# Sheet1.net
KiCad netlist of a schematic drawn in Altium Designer
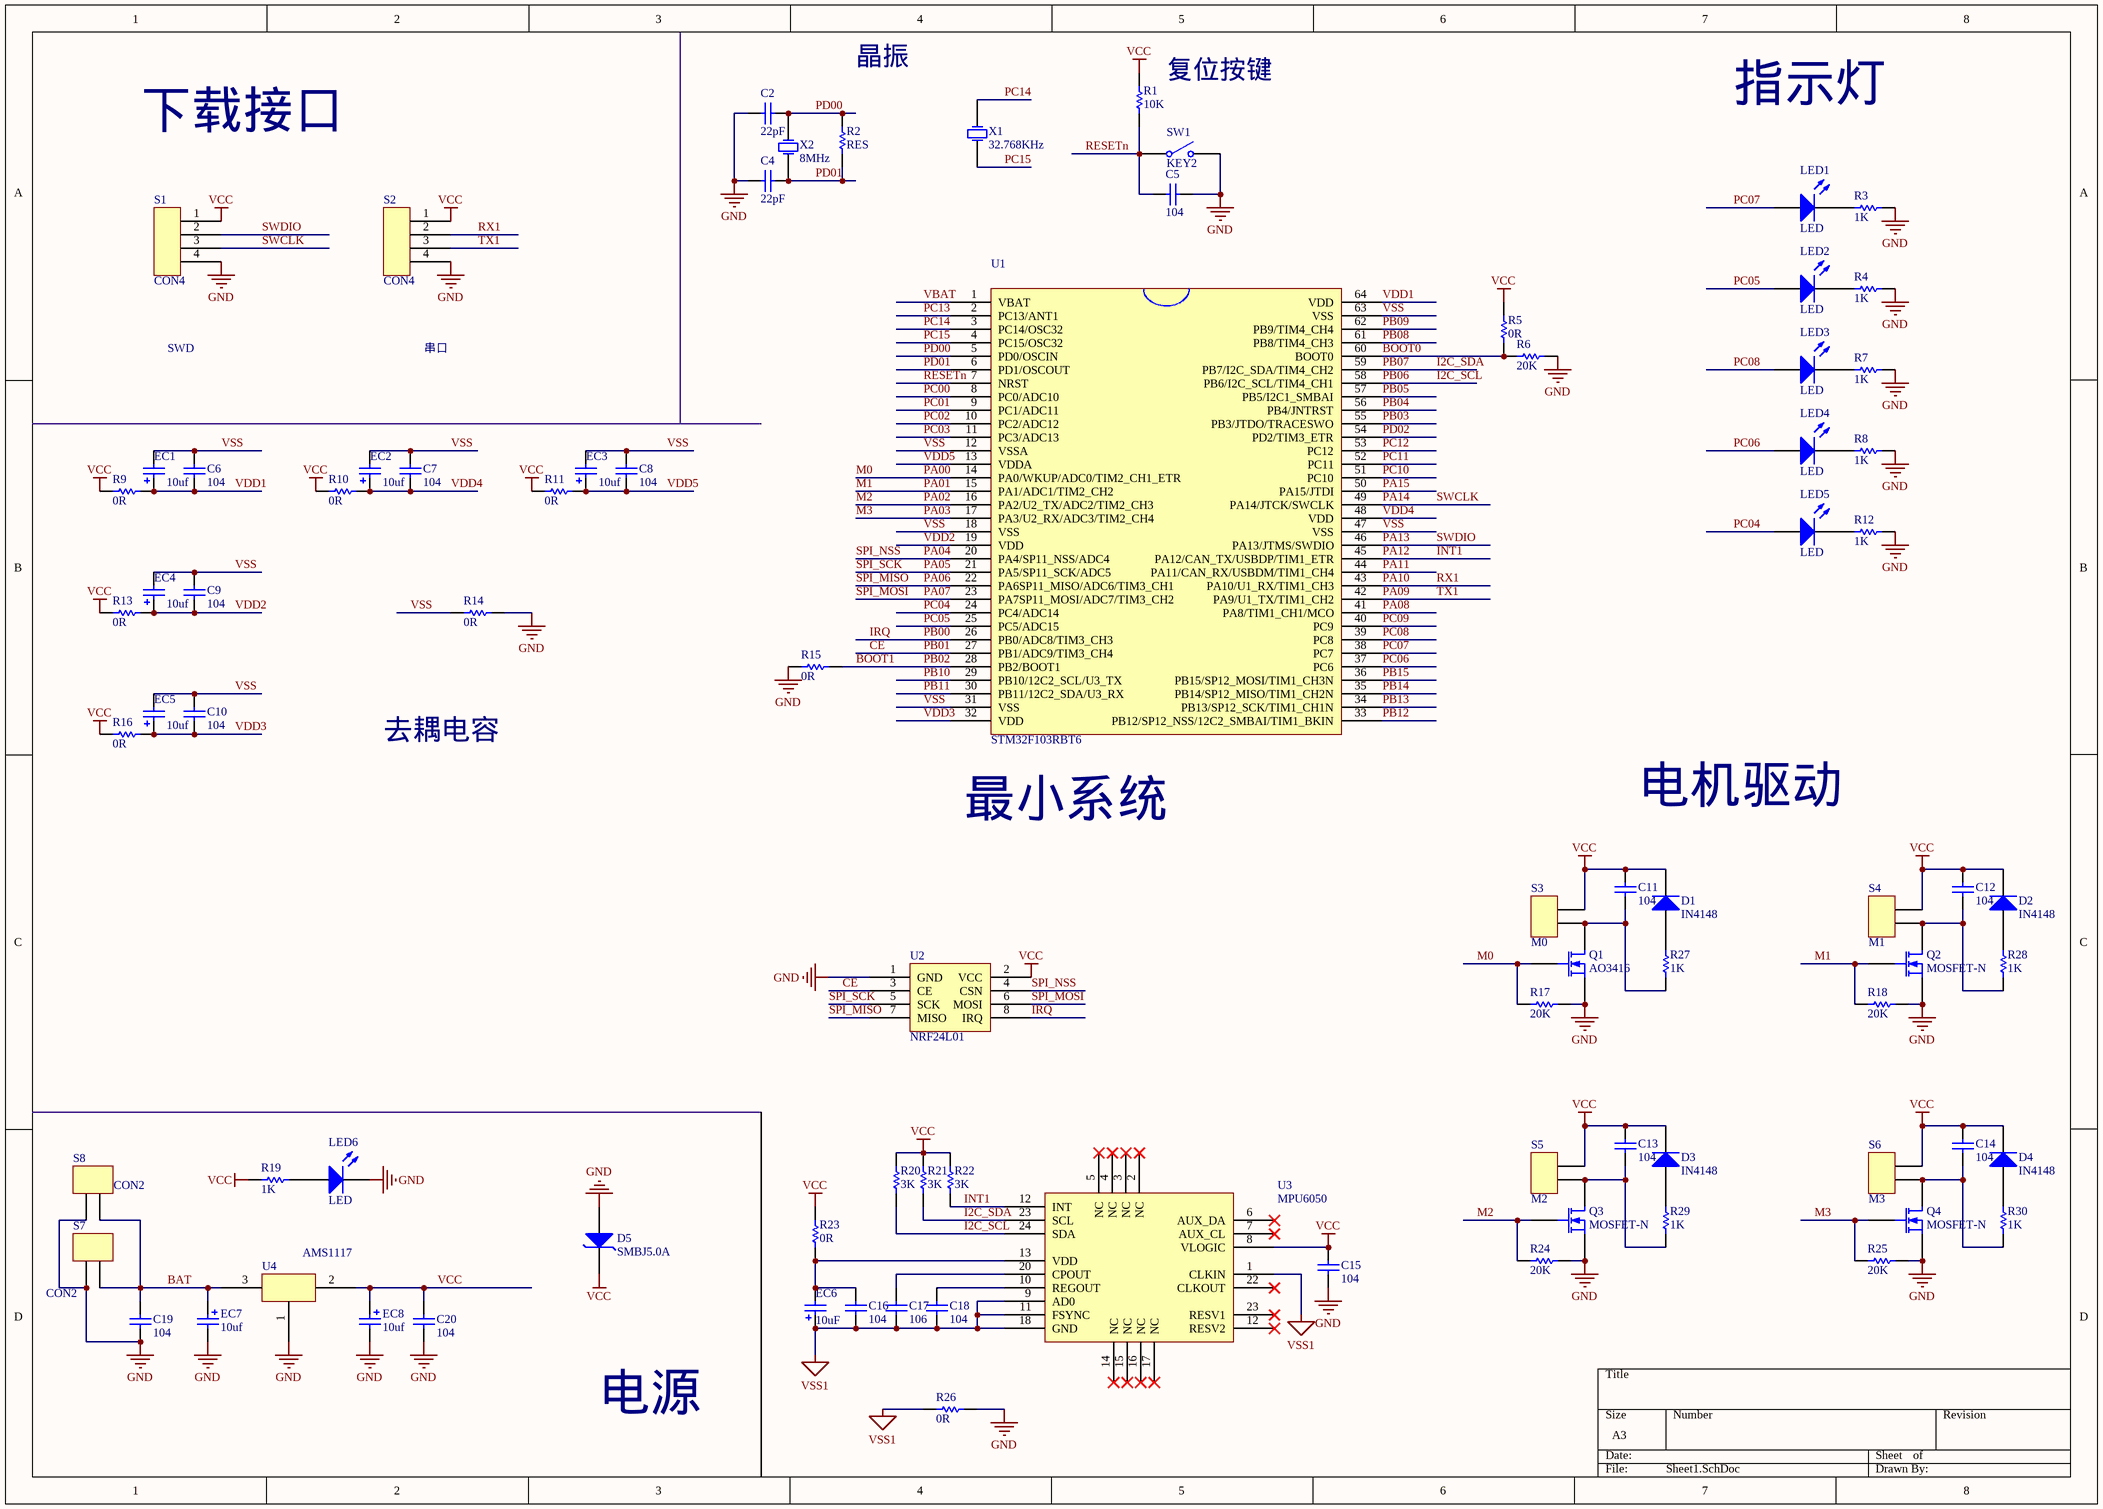
[diagram p0: Sheet1.SchDoc]

(export (version "E")
  (design (tool "Eeschema 10.0.6"))
  (components
    (comp (ref "C2") (value "22pF") (footprint "0805") (libsource (lib "yezi_sch") (part "CAP")))
    (comp (ref "C4") (value "22pF") (footprint "0805") (libsource (lib "yezi_sch") (part "CAP")))
    (comp (ref "C5") (value "104") (footprint "0603") (libsource (lib "yezi_sch") (part "CAP")))
    (comp (ref "C6") (value "104") (footprint "0603") (libsource (lib "yezi_sch") (part "CAP")))
    (comp (ref "C7") (value "104") (footprint "0603") (libsource (lib "yezi_sch") (part "CAP")))
    (comp (ref "C8") (value "104") (footprint "0603") (libsource (lib "yezi_sch") (part "CAP")))
    (comp (ref "C9") (value "104") (footprint "0603") (libsource (lib "yezi_sch") (part "CAP")))
    (comp (ref "C10") (value "104") (footprint "0603") (libsource (lib "yezi_sch") (part "CAP")))
    (comp (ref "C11") (value "104") (footprint "0603") (libsource (lib "yezi_sch") (part "CAP")))
    (comp (ref "C12") (value "104") (footprint "0603") (libsource (lib "yezi_sch") (part "CAP")))
    (comp (ref "C13") (value "104") (footprint "0603") (libsource (lib "yezi_sch") (part "CAP")))
    (comp (ref "C14") (value "104") (footprint "0603") (libsource (lib "yezi_sch") (part "CAP")))
    (comp (ref "C15") (value "104") (footprint "0603") (libsource (lib "yezi_sch") (part "CAP")))
    (comp (ref "C16") (value "104") (footprint "0603") (libsource (lib "yezi_sch") (part "CAP")))
    (comp (ref "C17") (value "106") (footprint "0805") (libsource (lib "yezi_sch") (part "CAP")))
    (comp (ref "C18") (value "104") (footprint "0603") (libsource (lib "yezi_sch") (part "CAP")))
    (comp (ref "C19") (value "104") (footprint "0603") (libsource (lib "yezi_sch") (part "CAP")))
    (comp (ref "C20") (value "104") (footprint "0603") (libsource (lib "yezi_sch") (part "CAP")))
    (comp (ref "D1") (value "IN4148") (footprint "1206") (libsource (lib "yezi_sch") (part "DIODE")))
    (comp (ref "D2") (value "IN4148") (footprint "1206") (libsource (lib "yezi_sch") (part "DIODE")))
    (comp (ref "D3") (value "IN4148") (footprint "1206") (libsource (lib "yezi_sch") (part "DIODE")))
    (comp (ref "D4") (value "IN4148") (footprint "1206") (libsource (lib "yezi_sch") (part "DIODE")))
    (comp (ref "D5")
      (value "SMBJ5.0A")
      (footprint "DIOM4436X23N")
      (libsource (lib "yezi_sch") (part "SMBJ5.0A"))
    )
    (comp (ref "EC1") (value "10uf") (footprint "1206") (libsource (lib "yezi_sch") (part "EC")))
    (comp (ref "EC2") (value "10uf") (footprint "1206") (libsource (lib "yezi_sch") (part "EC")))
    (comp (ref "EC3") (value "10uf") (footprint "1206") (libsource (lib "yezi_sch") (part "EC")))
    (comp (ref "EC4") (value "10uf") (footprint "1206") (libsource (lib "yezi_sch") (part "EC")))
    (comp (ref "EC5") (value "10uf") (footprint "1206") (libsource (lib "yezi_sch") (part "EC")))
    (comp (ref "EC6") (value "10uF") (footprint "1206") (libsource (lib "yezi_sch") (part "EC")))
    (comp (ref "EC7") (value "10uf") (footprint "1206") (libsource (lib "yezi_sch") (part "EC")))
    (comp (ref "EC8") (value "10uf") (footprint "1206") (libsource (lib "yezi_sch") (part "EC")))
    (comp (ref "LED1") (value "LED") (footprint "0805") (libsource (lib "yezi_sch") (part "LED")))
    (comp (ref "LED2") (value "LED") (footprint "0805") (libsource (lib "yezi_sch") (part "LED")))
    (comp (ref "LED3") (value "LED") (footprint "0805") (libsource (lib "yezi_sch") (part "LED")))
    (comp (ref "LED4") (value "LED") (footprint "0805") (libsource (lib "yezi_sch") (part "LED")))
    (comp (ref "LED5") (value "LED") (footprint "0805") (libsource (lib "yezi_sch") (part "LED")))
    (comp (ref "LED6") (value "LED") (footprint "0805") (libsource (lib "yezi_sch") (part "LED")))
    (comp (ref "Q1")
      (value "AO3416")
      (footprint "SOT-23_N")
      (description "N-Channel MOSFET")
      (fields (field (name "PUBLISHER") "Altium Limited"))
      (libsource (lib "yezi_sch") (part "MOSFET-N"))
    )
    (comp (ref "Q2")
      (value "MOSFET-N")
      (footprint "SOT-23_N")
      (description "N-Channel MOSFET")
      (fields (field (name "PUBLISHER") "Altium Limited"))
      (libsource (lib "yezi_sch") (part "MOSFET-N"))
    )
    (comp (ref "Q3")
      (value "MOSFET-N")
      (footprint "SOT-23_N")
      (description "N-Channel MOSFET")
      (fields (field (name "PUBLISHER") "Altium Limited"))
      (libsource (lib "yezi_sch") (part "MOSFET-N"))
    )
    (comp (ref "Q4")
      (value "MOSFET-N")
      (footprint "SOT-23_N")
      (description "N-Channel MOSFET")
      (fields (field (name "PUBLISHER") "Altium Limited"))
      (libsource (lib "yezi_sch") (part "MOSFET-N"))
    )
    (comp (ref "R1") (value "10K") (footprint "0603") (libsource (lib "yezi_sch") (part "RES")))
    (comp (ref "R2") (value "RES") (footprint "0805") (libsource (lib "yezi_sch") (part "RES")))
    (comp (ref "R3") (value "1K") (footprint "0603") (libsource (lib "yezi_sch") (part "RES")))
    (comp (ref "R4") (value "1K") (footprint "0603") (libsource (lib "yezi_sch") (part "RES")))
    (comp (ref "R5") (value "0R") (footprint "0603") (libsource (lib "yezi_sch") (part "RES")))
    (comp (ref "R6") (value "20K") (footprint "0603") (libsource (lib "yezi_sch") (part "RES")))
    (comp (ref "R7") (value "1K") (footprint "0603") (libsource (lib "yezi_sch") (part "RES")))
    (comp (ref "R8") (value "1K") (footprint "0603") (libsource (lib "yezi_sch") (part "RES")))
    (comp (ref "R9") (value "0R") (footprint "0603") (libsource (lib "yezi_sch") (part "RES")))
    (comp (ref "R10") (value "0R") (footprint "0603") (libsource (lib "yezi_sch") (part "RES")))
    (comp (ref "R11") (value "0R") (footprint "0603") (libsource (lib "yezi_sch") (part "RES")))
    (comp (ref "R12") (value "1K") (footprint "0603") (libsource (lib "yezi_sch") (part "RES")))
    (comp (ref "R13") (value "0R") (footprint "0603") (libsource (lib "yezi_sch") (part "RES")))
    (comp (ref "R14") (value "0R") (footprint "0603") (libsource (lib "yezi_sch") (part "RES")))
    (comp (ref "R15") (value "0R") (footprint "0603") (libsource (lib "yezi_sch") (part "RES")))
    (comp (ref "R16") (value "0R") (footprint "0603") (libsource (lib "yezi_sch") (part "RES")))
    (comp (ref "R17") (value "20K") (footprint "0603") (libsource (lib "yezi_sch") (part "RES")))
    (comp (ref "R18") (value "20K") (footprint "0603") (libsource (lib "yezi_sch") (part "RES")))
    (comp (ref "R19") (value "1K") (footprint "0603") (libsource (lib "yezi_sch") (part "RES")))
    (comp (ref "R20") (value "3K") (footprint "0603") (libsource (lib "yezi_sch") (part "RES")))
    (comp (ref "R21") (value "3K") (footprint "0603") (libsource (lib "yezi_sch") (part "RES")))
    (comp (ref "R22") (value "3K") (footprint "0603") (libsource (lib "yezi_sch") (part "RES")))
    (comp (ref "R23") (value "0R") (footprint "0603") (libsource (lib "yezi_sch") (part "RES")))
    (comp (ref "R24") (value "20K") (footprint "0603") (libsource (lib "yezi_sch") (part "RES")))
    (comp (ref "R25") (value "20K") (footprint "0603") (libsource (lib "yezi_sch") (part "RES")))
    (comp (ref "R26") (value "0R") (footprint "0603") (libsource (lib "yezi_sch") (part "RES")))
    (comp (ref "R27") (value "1K") (footprint "0603") (libsource (lib "yezi_sch") (part "RES")))
    (comp (ref "R28") (value "1K") (footprint "0603") (libsource (lib "yezi_sch") (part "RES")))
    (comp (ref "R29") (value "1K") (footprint "0603") (libsource (lib "yezi_sch") (part "RES")))
    (comp (ref "R30") (value "1K") (footprint "0603") (libsource (lib "yezi_sch") (part "RES")))
    (comp (ref "S1") (value "CON4") (footprint "SIP4") (libsource (lib "yezi_sch") (part "CON4")))
    (comp (ref "S2") (value "CON4") (footprint "SIP4") (libsource (lib "yezi_sch") (part "CON4")))
    (comp (ref "S3") (value "M0") (footprint "0805") (libsource (lib "yezi_sch") (part "CON2")))
    (comp (ref "S4") (value "M1") (footprint "0805") (libsource (lib "yezi_sch") (part "CON2")))
    (comp (ref "S5") (value "M2") (footprint "0805") (libsource (lib "yezi_sch") (part "CON2")))
    (comp (ref "S6") (value "M3") (footprint "0805") (libsource (lib "yezi_sch") (part "CON2")))
    (comp (ref "S7") (value "CON2") (footprint "1206") (libsource (lib "") (part "CON2_1")))
    (comp (ref "S8") (value "CON2") (footprint "SIP2") (libsource (lib "") (part "CON2_1")))
    (comp (ref "SW1") (value "KEY2") (footprint "SSOP2N") (libsource (lib "yezi_sch") (part "KEY2")))
    (comp (ref "U1")
      (value "STM32F103RBT6")
      (footprint "TSQFP50P1200X1200X160-64N")
      (libsource (lib "yezi_sch") (part "STM32F103RBT6"))
    )
    (comp (ref "U2") (value "NRF24L01") (footprint "CN8") (libsource (lib "yezi_sch") (part "NRF24L01")))
    (comp (ref "U3")
      (value "MPU6050")
      (footprint "QFN50P400X400X95_HS-25N")
      (libsource (lib "yezi_sch") (part "MPU6050"))
    )
    (comp (ref "U4") (value "AMS1117") (footprint "SOT223") (libsource (lib "yezi_sch") (part "AMS1117")))
    (comp (ref "X1") (value "32.768KHz") (footprint "XTAL-50-2") (libsource (lib "yezi_sch") (part "XTAL")))
    (comp (ref "X2") (value "8MHz") (footprint "XTAL-200") (libsource (lib "yezi_sch") (part "XTAL")))
  )
  (nets
    (net (code "1") (name "/BAT") (class "Default")
      (node (ref "C19") (pin "1") (pinfunction "1_1") (pintype "passive"))
      (node (ref "EC7") (pin "1") (pinfunction "1_1") (pintype "passive"))
      (node (ref "S7") (pin "1") (pinfunction "1_1") (pintype "passive"))
      (node (ref "S8") (pin "1") (pinfunction "1_1") (pintype "passive"))
      (node (ref "U4") (pin "3") (pinfunction "3_3") (pintype "passive"))
    )
    (net (code "2") (name "/BOOT0") (class "Default")
      (node (ref "R5") (pin "1") (pinfunction "1_1") (pintype "passive"))
      (node (ref "R6") (pin "1") (pinfunction "1_1") (pintype "passive"))
      (node (ref "U1") (pin "60") (pinfunction "BOOT0_60") (pintype "passive"))
    )
    (net (code "3") (name "/BOOT1") (class "Default")
      (node (ref "R15") (pin "2") (pinfunction "2_2") (pintype "passive"))
      (node (ref "U1") (pin "28") (pinfunction "PB2/BOOT1_28") (pintype "passive"))
    )
    (net (code "4") (name "/CE") (class "Default")
      (node (ref "U1") (pin "27") (pinfunction "PB1/ADC9/TIM3_CH4_27") (pintype "passive"))
      (node (ref "U2") (pin "3") (pinfunction "CE_3") (pintype "passive"))
    )
    (net (code "5") (name "/I2C_SCL") (class "Default")
      (node (ref "R20") (pin "1") (pinfunction "1_1") (pintype "passive"))
      (node (ref "U1") (pin "58") (pinfunction "PB6/I2C_SCL/TIM4_CH1_58") (pintype "passive"))
      (node (ref "U3") (pin "24") (pinfunction "SDA_24") (pintype "passive"))
    )
    (net (code "6") (name "/I2C_SDA") (class "Default")
      (node (ref "R21") (pin "1") (pinfunction "1_1") (pintype "passive"))
      (node (ref "U1") (pin "59") (pinfunction "PB7/I2C_SDA/TIM4_CH2_59") (pintype "passive"))
      (node (ref "U3") (pin "23") (pinfunction "SCL_23") (pintype "passive"))
    )
    (net (code "7") (name "/INT1") (class "Default")
      (node (ref "R22") (pin "1") (pinfunction "1_1") (pintype "passive"))
      (node (ref "U1") (pin "45") (pinfunction "PA12/CAN_TX/USBDP/TIM1_ETR_45") (pintype "passive"))
      (node (ref "U3") (pin "12") (pinfunction "INT_12") (pintype "passive"))
    )
    (net (code "8") (name "/IRQ") (class "Default")
      (node (ref "U1") (pin "26") (pinfunction "PB0/ADC8/TIM3_CH3_26") (pintype "passive"))
      (node (ref "U2") (pin "8") (pinfunction "IRQ_8") (pintype "passive"))
    )
    (net (code "9") (name "/M0") (class "Default")
      (node (ref "Q1") (pin "2") (pinfunction "G_2") (pintype "passive"))
      (node (ref "R17") (pin "1") (pinfunction "1_1") (pintype "passive"))
      (node (ref "U1") (pin "14") (pinfunction "PA0/WKUP/ADC0/TIM2_CH1_ETR_14") (pintype "passive"))
    )
    (net (code "10") (name "/M1") (class "Default")
      (node (ref "Q2") (pin "2") (pinfunction "G_2") (pintype "passive"))
      (node (ref "R18") (pin "1") (pinfunction "1_1") (pintype "passive"))
      (node (ref "U1") (pin "15") (pinfunction "PA1/ADC1/TIM2_CH2_15") (pintype "passive"))
    )
    (net (code "11") (name "/M2") (class "Default")
      (node (ref "Q3") (pin "2") (pinfunction "G_2") (pintype "passive"))
      (node (ref "R24") (pin "1") (pinfunction "1_1") (pintype "passive"))
      (node (ref "U1") (pin "16") (pinfunction "PA2/U2_TX/ADC2/TIM2_CH3_16") (pintype "passive"))
    )
    (net (code "12") (name "/M3") (class "Default")
      (node (ref "Q4") (pin "2") (pinfunction "G_2") (pintype "passive"))
      (node (ref "R25") (pin "1") (pinfunction "1_1") (pintype "passive"))
      (node (ref "U1") (pin "17") (pinfunction "PA3/U2_RX/ADC3/TIM2_CH4_17") (pintype "passive"))
    )
    (net (code "13") (name "/PA04") (class "Default")
      (node (ref "U1") (pin "20") (pinfunction "PA4/SP11_NSS/ADC4_20") (pintype "passive"))
      (node (ref "U2") (pin "4") (pinfunction "CSN_4") (pintype "passive"))
    )
    (net (code "14") (name "/PA05") (class "Default")
      (node (ref "U1") (pin "21") (pinfunction "PA5/SP11_SCK/ADC5_21") (pintype "passive"))
      (node (ref "U2") (pin "5") (pinfunction "SCK_5") (pintype "passive"))
    )
    (net (code "15") (name "/PA06") (class "Default")
      (node (ref "U1") (pin "22") (pinfunction "PA6SP11_MISO/ADC6/TIM3_CH1_22") (pintype "passive"))
      (node (ref "U2") (pin "7") (pinfunction "MISO_7") (pintype "passive"))
    )
    (net (code "16") (name "/PA07") (class "Default")
      (node (ref "U1") (pin "23") (pinfunction "PA7SP11_MOSI/ADC7/TIM3_CH2_23") (pintype "passive"))
      (node (ref "U2") (pin "6") (pinfunction "MOSI_6") (pintype "passive"))
    )
    (net (code "17") (name "/PA08") (class "Default")
      (node (ref "U1") (pin "41") (pinfunction "PA8/TIM1_CH1/MCO_41") (pintype "passive"))
    )
    (net (code "18") (name "/PA09") (class "Default")
      (node (ref "S2") (pin "3") (pinfunction "3_3") (pintype "passive"))
      (node (ref "U1") (pin "42") (pinfunction "PA9/U1_TX/TIM1_CH2_42") (pintype "passive"))
    )
    (net (code "19") (name "/PA10") (class "Default")
      (node (ref "S2") (pin "2") (pinfunction "2_2") (pintype "passive"))
      (node (ref "U1") (pin "43") (pinfunction "PA10/U1_RX/TIM1_CH3_43") (pintype "passive"))
    )
    (net (code "20") (name "/PA11") (class "Default")
      (node (ref "U1") (pin "44") (pinfunction "PA11/CAN_RX/USBDM/TIM1_CH4_44") (pintype "passive"))
    )
    (net (code "21") (name "/PA13") (class "Default")
      (node (ref "S1") (pin "2") (pinfunction "2_2") (pintype "passive"))
      (node (ref "U1") (pin "46") (pinfunction "PA13/JTMS/SWDIO_46") (pintype "passive"))
    )
    (net (code "22") (name "/PA14") (class "Default")
      (node (ref "S1") (pin "3") (pinfunction "3_3") (pintype "passive"))
      (node (ref "U1") (pin "49") (pinfunction "PA14/JTCK/SWCLK_49") (pintype "passive"))
    )
    (net (code "23") (name "/PA15") (class "Default")
      (node (ref "U1") (pin "50") (pinfunction "PA15/JTDI_50") (pintype "passive"))
    )
    (net (code "24") (name "/PB03") (class "Default")
      (node (ref "U1") (pin "55") (pinfunction "PB3/JTDO/TRACESWO_55") (pintype "passive"))
    )
    (net (code "25") (name "/PB04") (class "Default")
      (node (ref "U1") (pin "56") (pinfunction "PB4/JNTRST_56") (pintype "passive"))
    )
    (net (code "26") (name "/PB05") (class "Default")
      (node (ref "U1") (pin "57") (pinfunction "PB5/I2C1_SMBAI_57") (pintype "passive"))
    )
    (net (code "27") (name "/PB08") (class "Default")
      (node (ref "U1") (pin "61") (pinfunction "PB8/TIM4_CH3_61") (pintype "passive"))
    )
    (net (code "28") (name "/PB09") (class "Default")
      (node (ref "U1") (pin "62") (pinfunction "PB9/TIM4_CH4_62") (pintype "passive"))
    )
    (net (code "29") (name "/PB10") (class "Default")
      (node (ref "U1") (pin "29") (pinfunction "PB10/12C2_SCL/U3_TX_29") (pintype "passive"))
    )
    (net (code "30") (name "/PB11") (class "Default")
      (node (ref "U1") (pin "30") (pinfunction "PB11/12C2_SDA/U3_RX_30") (pintype "passive"))
    )
    (net (code "31") (name "/PB12") (class "Default")
      (node (ref "U1") (pin "33") (pinfunction "PB12/SP12_NSS/12C2_SMBAI/TIM1_BKIN_33") (pintype "passive"))
    )
    (net (code "32") (name "/PB13") (class "Default")
      (node (ref "U1") (pin "34") (pinfunction "PB13/SP12_SCK/TIM1_CH1N_34") (pintype "passive"))
    )
    (net (code "33") (name "/PB14") (class "Default")
      (node (ref "U1") (pin "35") (pinfunction "PB14/SP12_MISO/TIM1_CH2N_35") (pintype "passive"))
    )
    (net (code "34") (name "/PB15") (class "Default")
      (node (ref "U1") (pin "36") (pinfunction "PB15/SP12_MOSI/TIM1_CH3N_36") (pintype "passive"))
    )
    (net (code "35") (name "/PC00") (class "Default")
      (node (ref "U1") (pin "8") (pinfunction "PC0/ADC10_8") (pintype "passive"))
    )
    (net (code "36") (name "/PC01") (class "Default")
      (node (ref "U1") (pin "9") (pinfunction "PC1/ADC11_9") (pintype "passive"))
    )
    (net (code "37") (name "/PC02") (class "Default")
      (node (ref "U1") (pin "10") (pinfunction "PC2/ADC12_10") (pintype "passive"))
    )
    (net (code "38") (name "/PC03") (class "Default")
      (node (ref "U1") (pin "11") (pinfunction "PC3/ADC13_11") (pintype "passive"))
    )
    (net (code "39") (name "/PC04") (class "Default")
      (node (ref "LED5") (pin "1") (pinfunction "A_1") (pintype "passive"))
      (node (ref "U1") (pin "24") (pinfunction "PC4/ADC14_24") (pintype "passive"))
    )
    (net (code "40") (name "/PC05") (class "Default")
      (node (ref "LED2") (pin "1") (pinfunction "A_1") (pintype "passive"))
      (node (ref "U1") (pin "25") (pinfunction "PC5/ADC15_25") (pintype "passive"))
    )
    (net (code "41") (name "/PC06") (class "Default")
      (node (ref "LED4") (pin "1") (pinfunction "A_1") (pintype "passive"))
      (node (ref "U1") (pin "37") (pinfunction "PC6_37") (pintype "passive"))
    )
    (net (code "42") (name "/PC07") (class "Default")
      (node (ref "LED1") (pin "1") (pinfunction "A_1") (pintype "passive"))
      (node (ref "U1") (pin "38") (pinfunction "PC7_38") (pintype "passive"))
    )
    (net (code "43") (name "/PC08") (class "Default")
      (node (ref "LED3") (pin "1") (pinfunction "A_1") (pintype "passive"))
      (node (ref "U1") (pin "39") (pinfunction "PC8_39") (pintype "passive"))
    )
    (net (code "44") (name "/PC09") (class "Default")
      (node (ref "U1") (pin "40") (pinfunction "PC9_40") (pintype "passive"))
    )
    (net (code "45") (name "/PC10") (class "Default")
      (node (ref "U1") (pin "51") (pinfunction "PC10_51") (pintype "passive"))
    )
    (net (code "46") (name "/PC11") (class "Default")
      (node (ref "U1") (pin "52") (pinfunction "PC11_52") (pintype "passive"))
    )
    (net (code "47") (name "/PC12") (class "Default")
      (node (ref "U1") (pin "53") (pinfunction "PC12_53") (pintype "passive"))
    )
    (net (code "48") (name "/PC13") (class "Default")
      (node (ref "U1") (pin "2") (pinfunction "PC13/ANT1_2") (pintype "passive"))
    )
    (net (code "49") (name "/PC14") (class "Default")
      (node (ref "U1") (pin "3") (pinfunction "PC14/OSC32_3") (pintype "passive"))
      (node (ref "X1") (pin "2") (pinfunction "OSC2_2") (pintype "passive"))
    )
    (net (code "50") (name "/PC15") (class "Default")
      (node (ref "U1") (pin "4") (pinfunction "PC15/OSC32_4") (pintype "passive"))
      (node (ref "X1") (pin "1") (pinfunction "OSC1_1") (pintype "passive"))
    )
    (net (code "51") (name "/PD00") (class "Default")
      (node (ref "C2") (pin "2") (pinfunction "2_2") (pintype "passive"))
      (node (ref "R2") (pin "2") (pinfunction "2_2") (pintype "passive"))
      (node (ref "U1") (pin "5") (pinfunction "PD0/OSCIN_5") (pintype "passive"))
      (node (ref "X2") (pin "2") (pinfunction "OSC2_2") (pintype "passive"))
    )
    (net (code "52") (name "/PD01") (class "Default")
      (node (ref "C4") (pin "2") (pinfunction "2_2") (pintype "passive"))
      (node (ref "R2") (pin "1") (pinfunction "1_1") (pintype "passive"))
      (node (ref "U1") (pin "6") (pinfunction "PD1/OSCOUT_6") (pintype "passive"))
      (node (ref "X2") (pin "1") (pinfunction "OSC1_1") (pintype "passive"))
    )
    (net (code "53") (name "/PD02") (class "Default")
      (node (ref "U1") (pin "54") (pinfunction "PD2/TIM3_ETR_54") (pintype "passive"))
    )
    (net (code "54") (name "/RESETn") (class "Default")
      (node (ref "C5") (pin "1") (pinfunction "1_1") (pintype "passive"))
      (node (ref "R1") (pin "1") (pinfunction "1_1") (pintype "passive"))
      (node (ref "SW1") (pin "1") (pinfunction "COMMON1_1") (pintype "passive"))
      (node (ref "U1") (pin "7") (pinfunction "NRST_7") (pintype "passive"))
    )
    (net (code "55") (name "/VBAT") (class "Default")
      (node (ref "U1") (pin "1") (pinfunction "VBAT_1") (pintype "passive"))
    )
    (net (code "56") (name "/VDD1") (class "Default")
      (node (ref "C6") (pin "1") (pinfunction "1_1") (pintype "passive"))
      (node (ref "EC1") (pin "1") (pinfunction "1_1") (pintype "passive"))
      (node (ref "R9") (pin "2") (pinfunction "2_2") (pintype "passive"))
      (node (ref "U1") (pin "64") (pinfunction "VDD_64") (pintype "passive"))
    )
    (net (code "57") (name "/VDD2") (class "Default")
      (node (ref "C9") (pin "1") (pinfunction "1_1") (pintype "passive"))
      (node (ref "EC4") (pin "1") (pinfunction "1_1") (pintype "passive"))
      (node (ref "R13") (pin "2") (pinfunction "2_2") (pintype "passive"))
      (node (ref "U1") (pin "19") (pinfunction "VDD_19") (pintype "passive"))
    )
    (net (code "58") (name "/VDD3") (class "Default")
      (node (ref "C10") (pin "1") (pinfunction "1_1") (pintype "passive"))
      (node (ref "EC5") (pin "1") (pinfunction "1_1") (pintype "passive"))
      (node (ref "R16") (pin "2") (pinfunction "2_2") (pintype "passive"))
      (node (ref "U1") (pin "32") (pinfunction "VDD_32") (pintype "passive"))
    )
    (net (code "59") (name "/VDD4") (class "Default")
      (node (ref "C7") (pin "1") (pinfunction "1_1") (pintype "passive"))
      (node (ref "EC2") (pin "1") (pinfunction "1_1") (pintype "passive"))
      (node (ref "R10") (pin "2") (pinfunction "2_2") (pintype "passive"))
      (node (ref "U1") (pin "48") (pinfunction "VDD_48") (pintype "passive"))
    )
    (net (code "60") (name "/VDD5") (class "Default")
      (node (ref "C8") (pin "1") (pinfunction "1_1") (pintype "passive"))
      (node (ref "EC3") (pin "1") (pinfunction "1_1") (pintype "passive"))
      (node (ref "R11") (pin "2") (pinfunction "2_2") (pintype "passive"))
      (node (ref "U1") (pin "13") (pinfunction "VDDA_13") (pintype "passive"))
    )
    (net (code "61") (name "/VSS") (class "Default")
      (node (ref "C10") (pin "2") (pinfunction "2_2") (pintype "passive"))
      (node (ref "C6") (pin "2") (pinfunction "2_2") (pintype "passive"))
      (node (ref "C7") (pin "2") (pinfunction "2_2") (pintype "passive"))
      (node (ref "C8") (pin "2") (pinfunction "2_2") (pintype "passive"))
      (node (ref "C9") (pin "2") (pinfunction "2_2") (pintype "passive"))
      (node (ref "EC1") (pin "2") (pinfunction "2_2") (pintype "passive"))
      (node (ref "EC2") (pin "2") (pinfunction "2_2") (pintype "passive"))
      (node (ref "EC3") (pin "2") (pinfunction "2_2") (pintype "passive"))
      (node (ref "EC4") (pin "2") (pinfunction "2_2") (pintype "passive"))
      (node (ref "EC5") (pin "2") (pinfunction "2_2") (pintype "passive"))
      (node (ref "R14") (pin "1") (pinfunction "1_1") (pintype "passive"))
      (node (ref "U1") (pin "12") (pinfunction "VSSA_12") (pintype "passive"))
      (node (ref "U1") (pin "18") (pinfunction "VSS_18") (pintype "passive"))
      (node (ref "U1") (pin "31") (pinfunction "VSS_31") (pintype "passive"))
      (node (ref "U1") (pin "47") (pinfunction "VSS_47") (pintype "passive"))
      (node (ref "U1") (pin "63") (pinfunction "VSS_63") (pintype "passive"))
    )
    (net (code "62") (name "GND") (class "Default")
      (node (ref "C15") (pin "2") (pinfunction "2_2") (pintype "passive"))
      (node (ref "C19") (pin "2") (pinfunction "2_2") (pintype "passive"))
      (node (ref "C2") (pin "1") (pinfunction "1_1") (pintype "passive"))
      (node (ref "C20") (pin "2") (pinfunction "2_2") (pintype "passive"))
      (node (ref "C4") (pin "1") (pinfunction "1_1") (pintype "passive"))
      (node (ref "C5") (pin "2") (pinfunction "2_2") (pintype "passive"))
      (node (ref "D5") (pin "1") (pinfunction "A_1") (pintype "passive"))
      (node (ref "EC7") (pin "2") (pinfunction "2_2") (pintype "passive"))
      (node (ref "EC8") (pin "2") (pinfunction "2_2") (pintype "passive"))
      (node (ref "LED6") (pin "2") (pinfunction "K_2") (pintype "passive"))
      (node (ref "Q1") (pin "3") (pinfunction "S_3") (pintype "passive"))
      (node (ref "Q2") (pin "3") (pinfunction "S_3") (pintype "passive"))
      (node (ref "Q3") (pin "3") (pinfunction "S_3") (pintype "passive"))
      (node (ref "Q4") (pin "3") (pinfunction "S_3") (pintype "passive"))
      (node (ref "R12") (pin "2") (pinfunction "2_2") (pintype "passive"))
      (node (ref "R14") (pin "2") (pinfunction "2_2") (pintype "passive"))
      (node (ref "R15") (pin "1") (pinfunction "1_1") (pintype "passive"))
      (node (ref "R17") (pin "2") (pinfunction "2_2") (pintype "passive"))
      (node (ref "R18") (pin "2") (pinfunction "2_2") (pintype "passive"))
      (node (ref "R24") (pin "2") (pinfunction "2_2") (pintype "passive"))
      (node (ref "R25") (pin "2") (pinfunction "2_2") (pintype "passive"))
      (node (ref "R26") (pin "2") (pinfunction "2_2") (pintype "passive"))
      (node (ref "R3") (pin "2") (pinfunction "2_2") (pintype "passive"))
      (node (ref "R4") (pin "2") (pinfunction "2_2") (pintype "passive"))
      (node (ref "R6") (pin "2") (pinfunction "2_2") (pintype "passive"))
      (node (ref "R7") (pin "2") (pinfunction "2_2") (pintype "passive"))
      (node (ref "R8") (pin "2") (pinfunction "2_2") (pintype "passive"))
      (node (ref "S1") (pin "4") (pinfunction "4_4") (pintype "passive"))
      (node (ref "S2") (pin "4") (pinfunction "4_4") (pintype "passive"))
      (node (ref "S7") (pin "2") (pinfunction "2_2") (pintype "passive"))
      (node (ref "S8") (pin "2") (pinfunction "2_2") (pintype "passive"))
      (node (ref "SW1") (pin "2") (pinfunction "NO1_2") (pintype "passive"))
      (node (ref "U2") (pin "1") (pinfunction "GND_1") (pintype "passive"))
      (node (ref "U4") (pin "1") (pinfunction "1_1") (pintype "passive"))
    )
    (net (code "63") (name "Net-(D1-A)") (class "Default")
      (node (ref "D1") (pin "1") (pinfunction "A_1") (pintype "passive"))
      (node (ref "R27") (pin "2") (pinfunction "2_2") (pintype "passive"))
    )
    (net (code "64") (name "Net-(D2-A)") (class "Default")
      (node (ref "D2") (pin "1") (pinfunction "A_1") (pintype "passive"))
      (node (ref "R28") (pin "2") (pinfunction "2_2") (pintype "passive"))
    )
    (net (code "65") (name "Net-(D3-A)") (class "Default")
      (node (ref "D3") (pin "1") (pinfunction "A_1") (pintype "passive"))
      (node (ref "R29") (pin "2") (pinfunction "2_2") (pintype "passive"))
    )
    (net (code "66") (name "Net-(D4-A)") (class "Default")
      (node (ref "D4") (pin "1") (pinfunction "A_1") (pintype "passive"))
      (node (ref "R30") (pin "2") (pinfunction "2_2") (pintype "passive"))
    )
    (net (code "67") (name "Net-(LED1-K)") (class "Default")
      (node (ref "LED1") (pin "2") (pinfunction "K_2") (pintype "passive"))
      (node (ref "R3") (pin "1") (pinfunction "1_1") (pintype "passive"))
    )
    (net (code "68") (name "Net-(LED2-K)") (class "Default")
      (node (ref "LED2") (pin "2") (pinfunction "K_2") (pintype "passive"))
      (node (ref "R4") (pin "1") (pinfunction "1_1") (pintype "passive"))
    )
    (net (code "69") (name "Net-(LED3-K)") (class "Default")
      (node (ref "LED3") (pin "2") (pinfunction "K_2") (pintype "passive"))
      (node (ref "R7") (pin "1") (pinfunction "1_1") (pintype "passive"))
    )
    (net (code "70") (name "Net-(LED4-K)") (class "Default")
      (node (ref "LED4") (pin "2") (pinfunction "K_2") (pintype "passive"))
      (node (ref "R8") (pin "1") (pinfunction "1_1") (pintype "passive"))
    )
    (net (code "71") (name "Net-(LED5-K)") (class "Default")
      (node (ref "LED5") (pin "2") (pinfunction "K_2") (pintype "passive"))
      (node (ref "R12") (pin "1") (pinfunction "1_1") (pintype "passive"))
    )
    (net (code "72") (name "Net-(LED6-A)") (class "Default")
      (node (ref "LED6") (pin "1") (pinfunction "A_1") (pintype "passive"))
      (node (ref "R19") (pin "2") (pinfunction "2_2") (pintype "passive"))
    )
    (net (code "73") (name "Net-(Q1-D)") (class "Default")
      (node (ref "C11") (pin "1") (pinfunction "1_1") (pintype "passive"))
      (node (ref "Q1") (pin "1") (pinfunction "D_1") (pintype "passive"))
      (node (ref "R27") (pin "1") (pinfunction "1_1") (pintype "passive"))
      (node (ref "S3") (pin "2") (pinfunction "2_2") (pintype "passive"))
    )
    (net (code "74") (name "Net-(Q2-D)") (class "Default")
      (node (ref "C12") (pin "1") (pinfunction "1_1") (pintype "passive"))
      (node (ref "Q2") (pin "1") (pinfunction "D_1") (pintype "passive"))
      (node (ref "R28") (pin "1") (pinfunction "1_1") (pintype "passive"))
      (node (ref "S4") (pin "2") (pinfunction "2_2") (pintype "passive"))
    )
    (net (code "75") (name "Net-(Q3-D)") (class "Default")
      (node (ref "C13") (pin "1") (pinfunction "1_1") (pintype "passive"))
      (node (ref "Q3") (pin "1") (pinfunction "D_1") (pintype "passive"))
      (node (ref "R29") (pin "1") (pinfunction "1_1") (pintype "passive"))
      (node (ref "S5") (pin "2") (pinfunction "2_2") (pintype "passive"))
    )
    (net (code "76") (name "Net-(Q4-D)") (class "Default")
      (node (ref "C14") (pin "1") (pinfunction "1_1") (pintype "passive"))
      (node (ref "Q4") (pin "1") (pinfunction "D_1") (pintype "passive"))
      (node (ref "R30") (pin "1") (pinfunction "1_1") (pintype "passive"))
      (node (ref "S6") (pin "2") (pinfunction "2_2") (pintype "passive"))
    )
    (net (code "77") (name "Net-(U3-CPOUT)") (class "Default")
      (node (ref "C17") (pin "1") (pinfunction "1_1") (pintype "passive"))
      (node (ref "U3") (pin "20") (pinfunction "CPOUT_20") (pintype "passive"))
    )
    (net (code "78") (name "Net-(U3-REGOUT)") (class "Default")
      (node (ref "C18") (pin "1") (pinfunction "1_1") (pintype "passive"))
      (node (ref "U3") (pin "10") (pinfunction "REGOUT_10") (pintype "passive"))
    )
    (net (code "79") (name "Net-(U3-VDD)") (class "Default")
      (node (ref "C16") (pin "2") (pinfunction "2_2") (pintype "passive"))
      (node (ref "EC6") (pin "2") (pinfunction "2_2") (pintype "passive"))
      (node (ref "R23") (pin "1") (pinfunction "1_1") (pintype "passive"))
      (node (ref "U3") (pin "13") (pinfunction "VDD_13") (pintype "passive"))
    )
    (net (code "80") (name "VCC") (class "Default")
      (node (ref "C11") (pin "2") (pinfunction "2_2") (pintype "passive"))
      (node (ref "C12") (pin "2") (pinfunction "2_2") (pintype "passive"))
      (node (ref "C13") (pin "2") (pinfunction "2_2") (pintype "passive"))
      (node (ref "C14") (pin "2") (pinfunction "2_2") (pintype "passive"))
      (node (ref "C15") (pin "1") (pinfunction "1_1") (pintype "passive"))
      (node (ref "C20") (pin "1") (pinfunction "1_1") (pintype "passive"))
      (node (ref "D1") (pin "2") (pinfunction "K_2") (pintype "passive"))
      (node (ref "D2") (pin "2") (pinfunction "K_2") (pintype "passive"))
      (node (ref "D3") (pin "2") (pinfunction "K_2") (pintype "passive"))
      (node (ref "D4") (pin "2") (pinfunction "K_2") (pintype "passive"))
      (node (ref "D5") (pin "2") (pinfunction "K_2") (pintype "passive"))
      (node (ref "EC8") (pin "1") (pinfunction "1_1") (pintype "passive"))
      (node (ref "R1") (pin "2") (pinfunction "2_2") (pintype "passive"))
      (node (ref "R10") (pin "1") (pinfunction "1_1") (pintype "passive"))
      (node (ref "R11") (pin "1") (pinfunction "1_1") (pintype "passive"))
      (node (ref "R13") (pin "1") (pinfunction "1_1") (pintype "passive"))
      (node (ref "R16") (pin "1") (pinfunction "1_1") (pintype "passive"))
      (node (ref "R19") (pin "1") (pinfunction "1_1") (pintype "passive"))
      (node (ref "R20") (pin "2") (pinfunction "2_2") (pintype "passive"))
      (node (ref "R21") (pin "2") (pinfunction "2_2") (pintype "passive"))
      (node (ref "R22") (pin "2") (pinfunction "2_2") (pintype "passive"))
      (node (ref "R23") (pin "2") (pinfunction "2_2") (pintype "passive"))
      (node (ref "R5") (pin "2") (pinfunction "2_2") (pintype "passive"))
      (node (ref "R9") (pin "1") (pinfunction "1_1") (pintype "passive"))
      (node (ref "S1") (pin "1") (pinfunction "1_1") (pintype "passive"))
      (node (ref "S2") (pin "1") (pinfunction "1_1") (pintype "passive"))
      (node (ref "S3") (pin "1") (pinfunction "1_1") (pintype "passive"))
      (node (ref "S4") (pin "1") (pinfunction "1_1") (pintype "passive"))
      (node (ref "S5") (pin "1") (pinfunction "1_1") (pintype "passive"))
      (node (ref "S6") (pin "1") (pinfunction "1_1") (pintype "passive"))
      (node (ref "U2") (pin "2") (pinfunction "VCC_2") (pintype "passive"))
      (node (ref "U3") (pin "8") (pinfunction "VLOGIC_8") (pintype "passive"))
      (node (ref "U4") (pin "2") (pinfunction "2_2") (pintype "passive"))
    )
    (net (code "81") (name "VSS1") (class "Default")
      (node (ref "C16") (pin "1") (pinfunction "1_1") (pintype "passive"))
      (node (ref "C17") (pin "2") (pinfunction "2_2") (pintype "passive"))
      (node (ref "C18") (pin "2") (pinfunction "2_2") (pintype "passive"))
      (node (ref "EC6") (pin "1") (pinfunction "1_1") (pintype "passive"))
      (node (ref "R26") (pin "1") (pinfunction "1_1") (pintype "passive"))
      (node (ref "U3") (pin "1") (pinfunction "CLKIN_1") (pintype "passive"))
      (node (ref "U3") (pin "11") (pinfunction "FSYNC_11") (pintype "passive"))
      (node (ref "U3") (pin "18") (pinfunction "GND_18") (pintype "passive"))
      (node (ref "U3") (pin "9") (pinfunction "AD0_9") (pintype "passive"))
    )
    (net (code "82") (name "unconnected-(U3-AUX_CL-Pad7)") (class "Default")
      (node (ref "U3") (pin "7") (pinfunction "AUX_CL_7") (pintype "passive+no_connect"))
    )
    (net (code "83") (name "unconnected-(U3-AUX_DA-Pad6)") (class "Default")
      (node (ref "U3") (pin "6") (pinfunction "AUX_DA_6") (pintype "passive+no_connect"))
    )
    (net (code "84") (name "unconnected-(U3-CLKOUT-Pad22)") (class "Default")
      (node (ref "U3") (pin "22") (pinfunction "CLKOUT_22") (pintype "passive+no_connect"))
    )
    (net (code "85") (name "unconnected-(U3-NC-Pad2)") (class "Default")
      (node (ref "U3") (pin "2") (pinfunction "NC_2") (pintype "passive+no_connect"))
    )
    (net (code "86") (name "unconnected-(U3-NC-Pad3)") (class "Default")
      (node (ref "U3") (pin "3") (pinfunction "NC_3") (pintype "passive+no_connect"))
    )
    (net (code "87") (name "unconnected-(U3-NC-Pad4)") (class "Default")
      (node (ref "U3") (pin "4") (pinfunction "NC_4") (pintype "passive+no_connect"))
    )
    (net (code "88") (name "unconnected-(U3-NC-Pad5)") (class "Default")
      (node (ref "U3") (pin "5") (pinfunction "NC_5") (pintype "passive+no_connect"))
    )
    (net (code "89") (name "unconnected-(U3-NC-Pad14)") (class "Default")
      (node (ref "U3") (pin "14") (pinfunction "NC_14") (pintype "passive+no_connect"))
    )
    (net (code "90") (name "unconnected-(U3-NC-Pad15)") (class "Default")
      (node (ref "U3") (pin "15") (pinfunction "NC_15") (pintype "passive+no_connect"))
    )
    (net (code "91") (name "unconnected-(U3-NC-Pad16)") (class "Default")
      (node (ref "U3") (pin "16") (pinfunction "NC_16") (pintype "passive+no_connect"))
    )
    (net (code "92") (name "unconnected-(U3-NC-Pad17)") (class "Default")
      (node (ref "U3") (pin "17") (pinfunction "NC_17") (pintype "passive+no_connect"))
    )
    (net (code "93") (name "unconnected-(U3-RESV1-Pad23)") (class "Default")
      (node (ref "U3") (pin "23") (pinfunction "RESV1_23") (pintype "passive+no_connect"))
    )
    (net (code "94") (name "unconnected-(U3-RESV2-Pad12)") (class "Default")
      (node (ref "U3") (pin "12") (pinfunction "RESV2_12") (pintype "passive+no_connect"))
    )
    (net (code "95") (name "unconnected-(U4-Pad4)") (class "Default")
      (node (ref "U4") (pin "4") (pinfunction "4_4") (pintype "passive"))
    )
  )
)
